# Gain_Control.net
KiCad netlist of a schematic drawn in Altium Designer
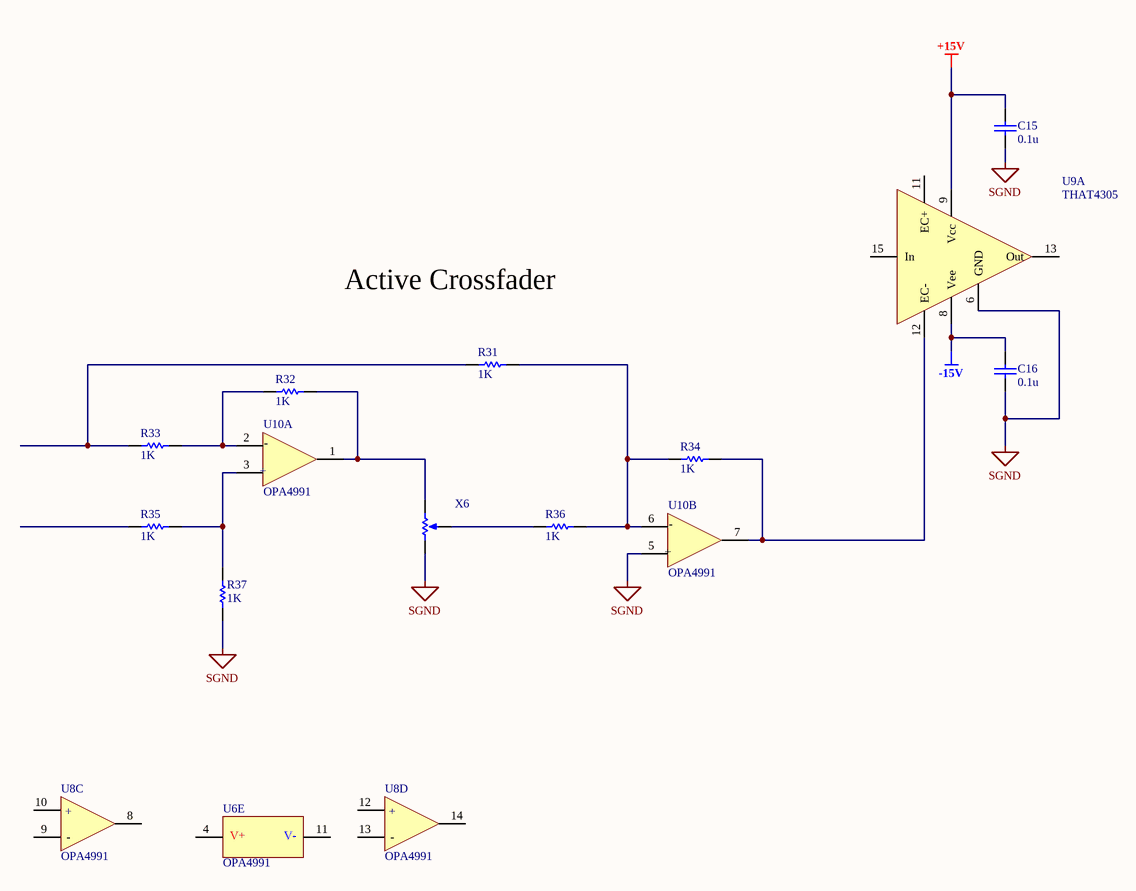
[diagram p0: Gain Control.SchDoc]

(export (version "E")
  (design (tool "Eeschema 10.0.6"))
  (components
    (comp (ref "C15")
      (value "0.1u")
      (description "Capacitor")
      (libsource (lib "Simulation Generic Components") (part "Capacitor"))
    )
    (comp (ref "C16")
      (value "0.1u")
      (description "Capacitor")
      (libsource (lib "Simulation Generic Components") (part "Capacitor"))
    )
    (comp (ref "R31")
      (value "1K")
      (description "Resistor")
      (libsource (lib "Simulation Generic Components") (part "Resistor"))
    )
    (comp (ref "R32")
      (value "1K")
      (description "Resistor")
      (libsource (lib "Simulation Generic Components") (part "Resistor"))
    )
    (comp (ref "R33")
      (value "1K")
      (description "Resistor")
      (libsource (lib "Simulation Generic Components") (part "Resistor"))
    )
    (comp (ref "R34")
      (value "1K")
      (description "Resistor")
      (libsource (lib "Simulation Generic Components") (part "Resistor"))
    )
    (comp (ref "R35")
      (value "1K")
      (description "Resistor")
      (libsource (lib "Simulation Generic Components") (part "Resistor"))
    )
    (comp (ref "R36")
      (value "1K")
      (description "Resistor")
      (libsource (lib "Simulation Generic Components") (part "Resistor"))
    )
    (comp (ref "R37")
      (value "1K")
      (description "Resistor")
      (libsource (lib "Simulation Generic Components") (part "Resistor"))
    )
    (comp (ref "U6")
      (value "OPA4991")
      (footprint "FP-D0014A-IPC_B")
      (description "40-V, DUAL 4.5MHZ, RAIL-TO-RAIL")
      (libsource (lib "DRC") (part "OPA4991IDR"))
    )
    (comp (ref "U8")
      (value "OPA4991")
      (footprint "FP-D0014A-IPC_B")
      (description "40-V, DUAL 4.5MHZ, RAIL-TO-RAIL")
      (libsource (lib "DRC") (part "OPA4991IDR"))
    )
    (comp (ref "U9")
      (value "THAT4305")
      (footprint "QSOP-16")
      (description "Pre-trimmed Analog Engine® Dynamics Processor IC")
      (libsource (lib "DRC") (part "4305Q16-U"))
    )
    (comp (ref "U10")
      (value "OPA4991")
      (footprint "FP-D0014A-IPC_B")
      (description "40-V, DUAL 4.5MHZ, RAIL-TO-RAIL")
      (libsource (lib "") (part "OPA4991IDR_1"))
    )
    (comp (ref "X6")
      (value "Potentiometer")
      (libsource (lib "Simulation Generic Components") (part "Potentiometer"))
    )
  )
  (nets
    (net (code "1") (name "+15V") (class "Default")
      (node (ref "C15") (pin "2") (pinfunction "2_2") (pintype "passive"))
      (node (ref "U9") (pin "9") (pinfunction "Vcc_9") (pintype "passive"))
    )
    (net (code "2") (name "-15V") (class "Default")
      (node (ref "C16") (pin "2") (pinfunction "2_2") (pintype "passive"))
      (node (ref "U9") (pin "8") (pinfunction "Vee_8") (pintype "passive"))
    )
    (net (code "3") (name "Net-(R31-Pad1)") (class "Default")
      (node (ref "R31") (pin "1") (pinfunction "1_1") (pintype "passive"))
      (node (ref "R33") (pin "1") (pinfunction "1_1") (pintype "passive"))
    )
    (net (code "4") (name "Net-(U10A-IN1+)") (class "Default")
      (node (ref "R35") (pin "2") (pinfunction "2_2") (pintype "passive"))
      (node (ref "R37") (pin "2") (pinfunction "2_2") (pintype "passive"))
      (node (ref "U10") (pin "3") (pinfunction "IN1+_3") (pintype "tri_state"))
    )
    (net (code "5") (name "Net-(U10A-IN1-)") (class "Default")
      (node (ref "R32") (pin "1") (pinfunction "1_1") (pintype "passive"))
      (node (ref "R33") (pin "2") (pinfunction "2_2") (pintype "passive"))
      (node (ref "U10") (pin "2") (pinfunction "IN1-_2") (pintype "tri_state"))
    )
    (net (code "6") (name "Net-(U10A-OUT1)") (class "Default")
      (node (ref "R32") (pin "2") (pinfunction "2_2") (pintype "passive"))
      (node (ref "U10") (pin "1") (pinfunction "OUT1_1") (pintype "passive"))
      (node (ref "X6") (pin "2") (pinfunction "BOT_2") (pintype "passive"))
    )
    (net (code "7") (name "Net-(U10B-IN2-)") (class "Default")
      (node (ref "R31") (pin "2") (pinfunction "2_2") (pintype "passive"))
      (node (ref "R34") (pin "1") (pinfunction "1_1") (pintype "passive"))
      (node (ref "R36") (pin "2") (pinfunction "2_2") (pintype "passive"))
      (node (ref "U10") (pin "6") (pinfunction "IN2-_6") (pintype "tri_state"))
    )
    (net (code "8") (name "Net-(U10B-OUT2)") (class "Default")
      (node (ref "R34") (pin "2") (pinfunction "2_2") (pintype "passive"))
      (node (ref "U10") (pin "7") (pinfunction "OUT2_7") (pintype "passive"))
      (node (ref "U9") (pin "12") (pinfunction "EC-_12") (pintype "passive"))
    )
    (net (code "9") (name "Net-(X6-TAP)") (class "Default")
      (node (ref "R36") (pin "1") (pinfunction "1_1") (pintype "passive"))
      (node (ref "X6") (pin "3") (pinfunction "TAP_3") (pintype "passive"))
    )
    (net (code "10") (name "SGND") (class "Default")
      (node (ref "C15") (pin "1") (pinfunction "1_1") (pintype "passive"))
      (node (ref "C16") (pin "1") (pinfunction "1_1") (pintype "passive"))
      (node (ref "R37") (pin "1") (pinfunction "1_1") (pintype "passive"))
      (node (ref "U10") (pin "5") (pinfunction "IN2+_5") (pintype "tri_state"))
      (node (ref "U9") (pin "6") (pinfunction "GND_6") (pintype "passive"))
      (node (ref "X6") (pin "1") (pinfunction "TOP_1") (pintype "passive"))
    )
    (net (code "11") (name "unconnected-(R35-Pad1)") (class "Default")
      (node (ref "R35") (pin "1") (pinfunction "1_1") (pintype "passive"))
    )
    (net (code "12") (name "unconnected-(U6E-V+-Pad4)") (class "Default")
      (node (ref "U6") (pin "4") (pinfunction "V+_4") (pintype "power_in"))
    )
    (net (code "13") (name "unconnected-(U6E-V--Pad11)") (class "Default")
      (node (ref "U6") (pin "11") (pinfunction "V-_11") (pintype "power_in"))
    )
    (net (code "14") (name "unconnected-(U8C-IN3+-Pad10)") (class "Default")
      (node (ref "U8") (pin "10") (pinfunction "IN3+_10") (pintype "tri_state"))
    )
    (net (code "15") (name "unconnected-(U8C-IN3--Pad9)") (class "Default")
      (node (ref "U8") (pin "9") (pinfunction "IN3-_9") (pintype "tri_state"))
    )
    (net (code "16") (name "unconnected-(U8C-OUT3-Pad8)") (class "Default")
      (node (ref "U8") (pin "8") (pinfunction "OUT3_8") (pintype "passive"))
    )
    (net (code "17") (name "unconnected-(U8D-IN4+-Pad12)") (class "Default")
      (node (ref "U8") (pin "12") (pinfunction "IN4+_12") (pintype "tri_state"))
    )
    (net (code "18") (name "unconnected-(U8D-IN4--Pad13)") (class "Default")
      (node (ref "U8") (pin "13") (pinfunction "IN4-_13") (pintype "tri_state"))
    )
    (net (code "19") (name "unconnected-(U8D-OUT4-Pad14)") (class "Default")
      (node (ref "U8") (pin "14") (pinfunction "OUT4_14") (pintype "passive"))
    )
    (net (code "20") (name "unconnected-(U9A-EC+-Pad11)") (class "Default")
      (node (ref "U9") (pin "11") (pinfunction "EC+_11") (pintype "passive"))
    )
    (net (code "21") (name "unconnected-(U9A-In-Pad15)") (class "Default")
      (node (ref "U9") (pin "15") (pinfunction "In_15") (pintype "passive"))
    )
    (net (code "22") (name "unconnected-(U9A-Out-Pad13)") (class "Default")
      (node (ref "U9") (pin "13") (pinfunction "Out_13") (pintype "passive"))
    )
  )
)
